# sample.net
KiCad netlist of a schematic drawn in EAGLE
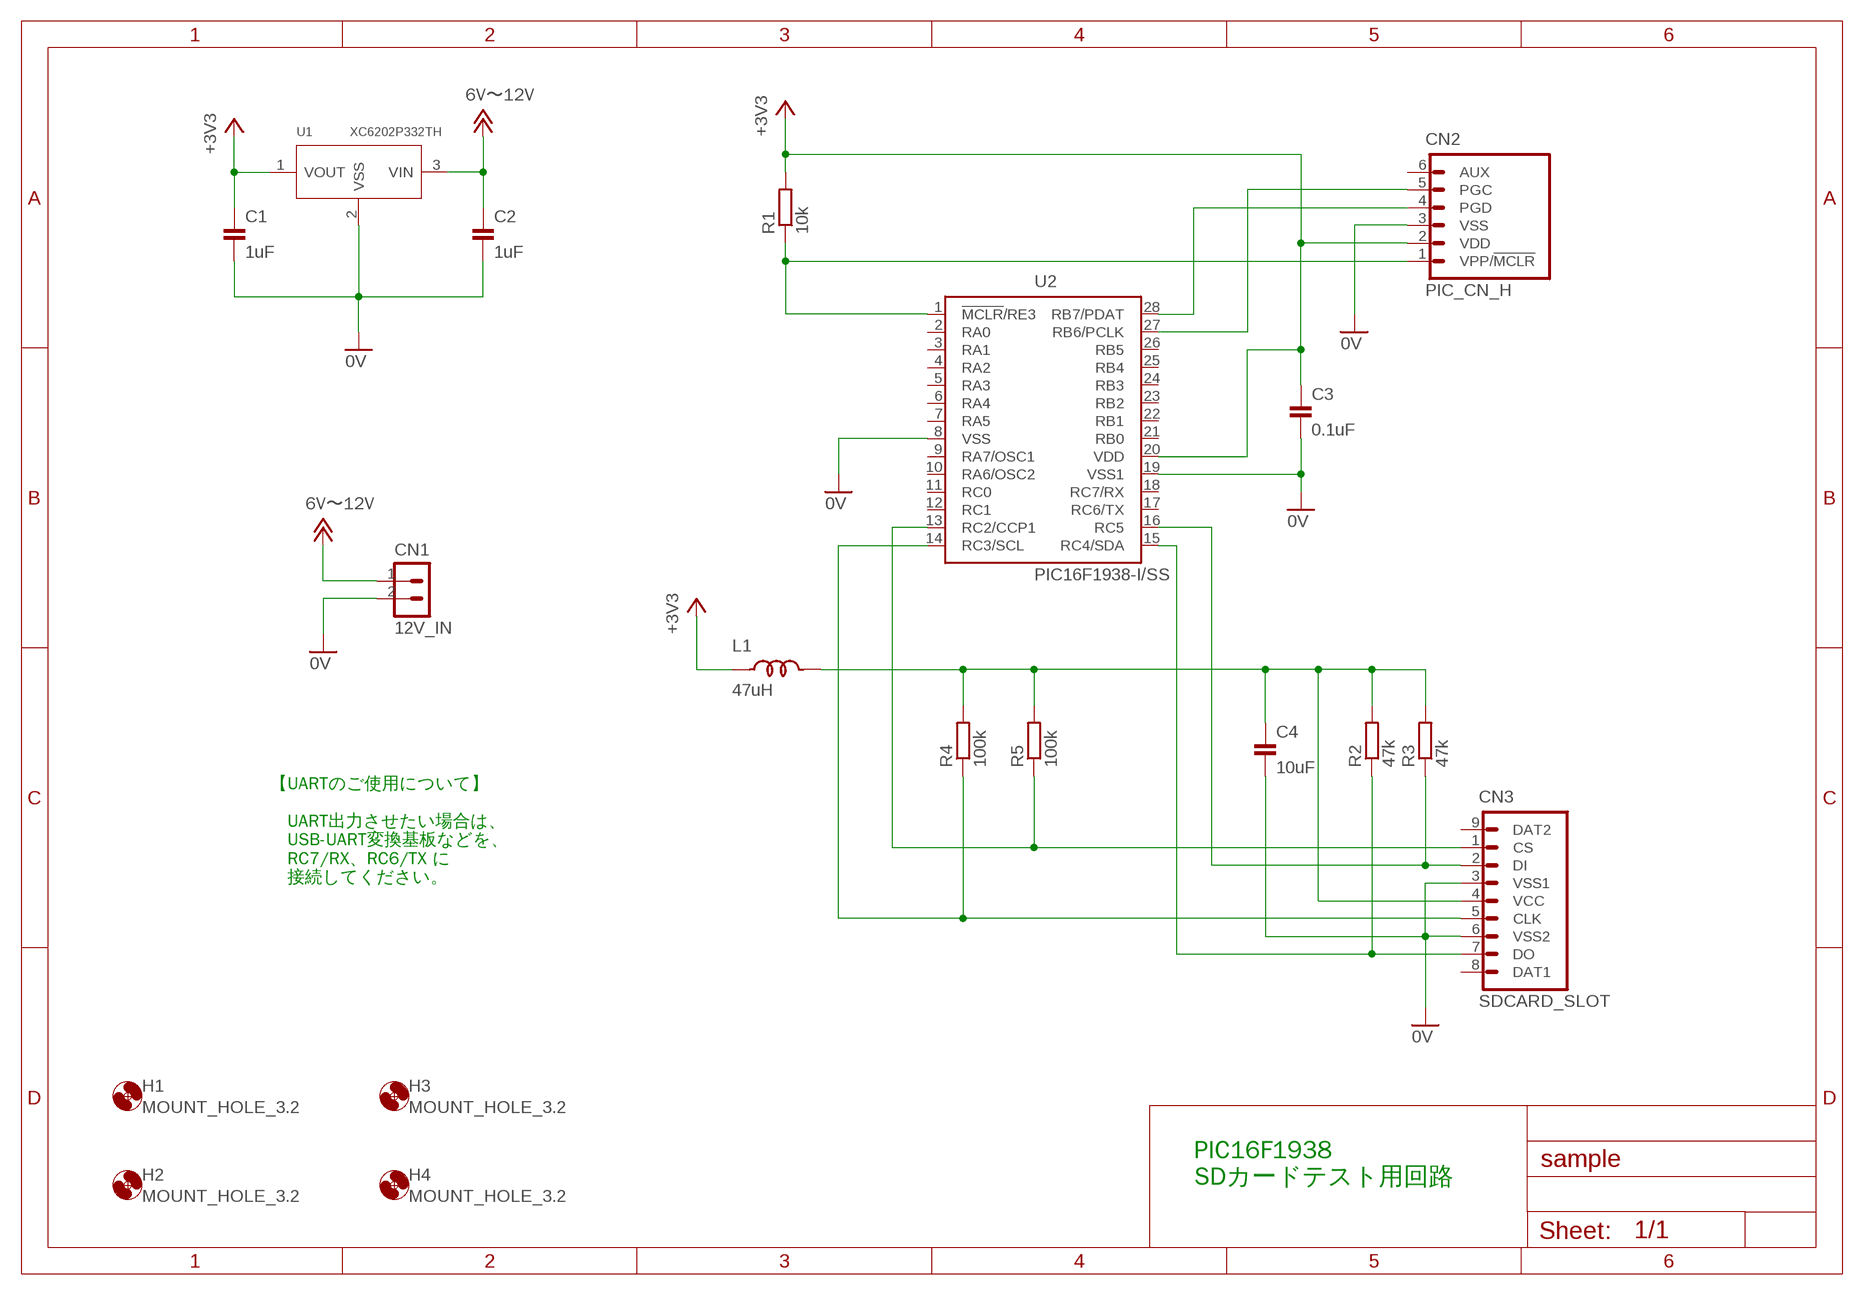
[diagram p0: schematic, sheet 1]

(export (version "E")
  (design (tool "Eeschema 10.0.6"))
  (components
    (comp (ref "C1")
      (value "1uF")
      (footprint "eagle-import:CAP_200MIL")
      (libsource (lib "eagle-import") (part "CAP_200MIL"))
    )
    (comp (ref "C2")
      (value "1uF")
      (footprint "eagle-import:CAP_200MIL")
      (libsource (lib "eagle-import") (part "CAP_200MIL"))
    )
    (comp (ref "C3")
      (value "0.1uF")
      (footprint "eagle-import:CAP_200MIL")
      (libsource (lib "eagle-import") (part "CAP_200MIL"))
    )
    (comp (ref "C4")
      (value "10uF")
      (footprint "eagle-import:CAP_200MIL")
      (libsource (lib "eagle-import") (part "CAP_200MIL"))
    )
    (comp (ref "CN1")
      (value "12V_IN")
      (footprint "eagle-import:HEADER_L_2PIN")
      (libsource (lib "eagle-import") (part "CONN_2PIN-L"))
    )
    (comp (ref "CN2")
      (value "PIC_CN_H")
      (footprint "eagle-import:HEADER_6PIN")
      (libsource (lib "eagle-import") (part "PIC_CN_H"))
    )
    (comp (ref "CN3")
      (value "SDCARD_SLOT")
      (footprint "eagle-import:SDCARD_SLOT")
      (libsource (lib "eagle-import") (part "SDCARD_SLOT"))
    )
    (comp (ref "H1")
      (value "MOUNT_HOLE_3.2")
      (footprint "eagle-import:3,2")
      (libsource (lib "eagle-import") (part "MOUNT_HOLE_3.2"))
    )
    (comp (ref "H2")
      (value "MOUNT_HOLE_3.2")
      (footprint "eagle-import:3,2")
      (libsource (lib "eagle-import") (part "MOUNT_HOLE_3.2"))
    )
    (comp (ref "H3")
      (value "MOUNT_HOLE_3.2")
      (footprint "eagle-import:3,2")
      (libsource (lib "eagle-import") (part "MOUNT_HOLE_3.2"))
    )
    (comp (ref "H4")
      (value "MOUNT_HOLE_3.2")
      (footprint "eagle-import:3,2")
      (libsource (lib "eagle-import") (part "MOUNT_HOLE_3.2"))
    )
    (comp (ref "L1")
      (value "47uH")
      (footprint "eagle-import:TOROID_COIL-300MIL")
      (libsource (lib "eagle-import") (part "TC5026-22UH-060"))
    )
    (comp (ref "R1")
      (value "10k")
      (footprint "eagle-import:RESISTOR_0207_300MIL")
      (libsource (lib "eagle-import") (part "RESISTOR_300MIL"))
    )
    (comp (ref "R2")
      (value "47k")
      (footprint "eagle-import:RESISTOR_0207_300MIL")
      (libsource (lib "eagle-import") (part "RESISTOR_300MIL"))
    )
    (comp (ref "R3")
      (value "47k")
      (footprint "eagle-import:RESISTOR_0207_300MIL")
      (libsource (lib "eagle-import") (part "RESISTOR_300MIL"))
    )
    (comp (ref "R4")
      (value "100k")
      (footprint "eagle-import:RESISTOR_0207_300MIL")
      (libsource (lib "eagle-import") (part "RESISTOR_300MIL"))
    )
    (comp (ref "R5")
      (value "100k")
      (footprint "eagle-import:RESISTOR_0207_300MIL")
      (libsource (lib "eagle-import") (part "RESISTOR_300MIL"))
    )
    (comp (ref "U1")
      (value "XC6202P332TH")
      (footprint "eagle-import:TO92-LINE")
      (libsource (lib "eagle-import") (part "XC6202P332TH"))
    )
    (comp (ref "U2")
      (value "PIC16F1938-I/SS")
      (footprint "eagle-import:SSOP28")
      (libsource (lib "eagle-import") (part "PIC16F1938-I/SS"))
    )
  )
  (nets
    (net (code "1") (name "+3V3") (class "Default")
      (node (ref "C1") (pin "1") (pinfunction "1_1") (pintype "passive"))
      (node (ref "C3") (pin "1") (pinfunction "1_1") (pintype "passive"))
      (node (ref "CN2") (pin "2") (pinfunction "VDD_2") (pintype "passive"))
      (node (ref "L1") (pin "1") (pinfunction "1_1") (pintype "passive"))
      (node (ref "R1") (pin "2") (pinfunction "2_2") (pintype "passive"))
      (node (ref "U1") (pin "1") (pinfunction "VOUT_1") (pintype "passive"))
      (node (ref "U2") (pin "20") (pinfunction "VDD_20") (pintype "passive"))
    )
    (net (code "2") (name "0V") (class "Default")
      (node (ref "C1") (pin "2") (pinfunction "2_2") (pintype "passive"))
      (node (ref "C2") (pin "2") (pinfunction "2_2") (pintype "passive"))
      (node (ref "C3") (pin "2") (pinfunction "2_2") (pintype "passive"))
      (node (ref "C4") (pin "2") (pinfunction "2_2") (pintype "passive"))
      (node (ref "CN1") (pin "2") (pinfunction "2_2") (pintype "passive"))
      (node (ref "CN2") (pin "3") (pinfunction "VSS_3") (pintype "passive"))
      (node (ref "CN3") (pin "3") (pinfunction "VSS1_3") (pintype "passive"))
      (node (ref "CN3") (pin "6") (pinfunction "VSS2_6") (pintype "passive"))
      (node (ref "U1") (pin "2") (pinfunction "VSS_2") (pintype "passive"))
      (node (ref "U2") (pin "19") (pinfunction "VSS1_19") (pintype "passive"))
      (node (ref "U2") (pin "8") (pinfunction "VSS_8") (pintype "passive"))
    )
    (net (code "3") (name "6V〜12V") (class "Default")
      (node (ref "C2") (pin "1") (pinfunction "1_1") (pintype "passive"))
      (node (ref "CN1") (pin "1") (pinfunction "1_1") (pintype "passive"))
      (node (ref "U1") (pin "3") (pinfunction "VIN_3") (pintype "passive"))
    )
    (net (code "4") (name "Net-(CN2-PGC)") (class "Default")
      (node (ref "CN2") (pin "5") (pinfunction "PGC_5") (pintype "input"))
      (node (ref "U2") (pin "27") (pinfunction "RB6/PCLK_27") (pintype "bidirectional"))
    )
    (net (code "5") (name "Net-(CN2-PGD)") (class "Default")
      (node (ref "CN2") (pin "4") (pinfunction "PGD_4") (pintype "bidirectional"))
      (node (ref "U2") (pin "28") (pinfunction "RB7/PDAT_28") (pintype "bidirectional"))
    )
    (net (code "6") (name "Net-(CN2-VPP{slash}~{MCLR})") (class "Default")
      (node (ref "CN2") (pin "1") (pinfunction "VPP/~{MCLR}_1") (pintype "input"))
      (node (ref "R1") (pin "1") (pinfunction "1_1") (pintype "passive"))
      (node (ref "U2") (pin "1") (pinfunction "~{MCLR}/RE3_1") (pintype "bidirectional"))
    )
    (net (code "7") (name "Net-(CN3-CLK)") (class "Default")
      (node (ref "CN3") (pin "5") (pinfunction "CLK_5") (pintype "bidirectional"))
      (node (ref "R4") (pin "1") (pinfunction "1_1") (pintype "passive"))
      (node (ref "U2") (pin "14") (pinfunction "RC3/SCL_14") (pintype "bidirectional"))
    )
    (net (code "8") (name "Net-(CN3-CS)") (class "Default")
      (node (ref "CN3") (pin "1") (pinfunction "CS_1") (pintype "bidirectional"))
      (node (ref "R5") (pin "1") (pinfunction "1_1") (pintype "passive"))
      (node (ref "U2") (pin "13") (pinfunction "RC2/CCP1_13") (pintype "bidirectional"))
    )
    (net (code "9") (name "Net-(CN3-DI)") (class "Default")
      (node (ref "CN3") (pin "2") (pinfunction "DI_2") (pintype "bidirectional"))
      (node (ref "R3") (pin "1") (pinfunction "1_1") (pintype "passive"))
      (node (ref "U2") (pin "16") (pinfunction "RC5_16") (pintype "bidirectional"))
    )
    (net (code "10") (name "Net-(CN3-DO)") (class "Default")
      (node (ref "CN3") (pin "7") (pinfunction "DO_7") (pintype "bidirectional"))
      (node (ref "R2") (pin "1") (pinfunction "1_1") (pintype "passive"))
      (node (ref "U2") (pin "15") (pinfunction "RC4/SDA_15") (pintype "bidirectional"))
    )
    (net (code "11") (name "Net-(CN3-VCC)") (class "Default")
      (node (ref "C4") (pin "1") (pinfunction "1_1") (pintype "passive"))
      (node (ref "CN3") (pin "4") (pinfunction "VCC_4") (pintype "passive"))
      (node (ref "L1") (pin "2") (pinfunction "2_2") (pintype "passive"))
      (node (ref "R2") (pin "2") (pinfunction "2_2") (pintype "passive"))
      (node (ref "R3") (pin "2") (pinfunction "2_2") (pintype "passive"))
      (node (ref "R4") (pin "2") (pinfunction "2_2") (pintype "passive"))
      (node (ref "R5") (pin "2") (pinfunction "2_2") (pintype "passive"))
    )
    (net (code "12") (name "unconnected-(CN2-AUX-Pad6)") (class "Default")
      (node (ref "CN2") (pin "6") (pinfunction "AUX_6") (pintype "bidirectional"))
    )
    (net (code "13") (name "unconnected-(CN3-DAT1-Pad8)") (class "Default")
      (node (ref "CN3") (pin "8") (pinfunction "DAT1_8") (pintype "bidirectional"))
    )
    (net (code "14") (name "unconnected-(CN3-DAT2-Pad9)") (class "Default")
      (node (ref "CN3") (pin "9") (pinfunction "DAT2_9") (pintype "bidirectional"))
    )
    (net (code "15") (name "unconnected-(U2-RA0-Pad2)") (class "Default")
      (node (ref "U2") (pin "2") (pinfunction "RA0_2") (pintype "bidirectional"))
    )
    (net (code "16") (name "unconnected-(U2-RA1-Pad3)") (class "Default")
      (node (ref "U2") (pin "3") (pinfunction "RA1_3") (pintype "bidirectional"))
    )
    (net (code "17") (name "unconnected-(U2-RA2-Pad4)") (class "Default")
      (node (ref "U2") (pin "4") (pinfunction "RA2_4") (pintype "bidirectional"))
    )
    (net (code "18") (name "unconnected-(U2-RA3-Pad5)") (class "Default")
      (node (ref "U2") (pin "5") (pinfunction "RA3_5") (pintype "bidirectional"))
    )
    (net (code "19") (name "unconnected-(U2-RA4-Pad6)") (class "Default")
      (node (ref "U2") (pin "6") (pinfunction "RA4_6") (pintype "bidirectional"))
    )
    (net (code "20") (name "unconnected-(U2-RA5-Pad7)") (class "Default")
      (node (ref "U2") (pin "7") (pinfunction "RA5_7") (pintype "bidirectional"))
    )
    (net (code "21") (name "unconnected-(U2-RA6{slash}OSC2-Pad10)") (class "Default")
      (node (ref "U2") (pin "10") (pinfunction "RA6/OSC2_10") (pintype "bidirectional"))
    )
    (net (code "22") (name "unconnected-(U2-RA7{slash}OSC1-Pad9)") (class "Default")
      (node (ref "U2") (pin "9") (pinfunction "RA7/OSC1_9") (pintype "bidirectional"))
    )
    (net (code "23") (name "unconnected-(U2-RB0-Pad21)") (class "Default")
      (node (ref "U2") (pin "21") (pinfunction "RB0_21") (pintype "bidirectional"))
    )
    (net (code "24") (name "unconnected-(U2-RB1-Pad22)") (class "Default")
      (node (ref "U2") (pin "22") (pinfunction "RB1_22") (pintype "bidirectional"))
    )
    (net (code "25") (name "unconnected-(U2-RB2-Pad23)") (class "Default")
      (node (ref "U2") (pin "23") (pinfunction "RB2_23") (pintype "bidirectional"))
    )
    (net (code "26") (name "unconnected-(U2-RB3-Pad24)") (class "Default")
      (node (ref "U2") (pin "24") (pinfunction "RB3_24") (pintype "bidirectional"))
    )
    (net (code "27") (name "unconnected-(U2-RB4-Pad25)") (class "Default")
      (node (ref "U2") (pin "25") (pinfunction "RB4_25") (pintype "bidirectional"))
    )
    (net (code "28") (name "unconnected-(U2-RB5-Pad26)") (class "Default")
      (node (ref "U2") (pin "26") (pinfunction "RB5_26") (pintype "bidirectional"))
    )
    (net (code "29") (name "unconnected-(U2-RC0-Pad11)") (class "Default")
      (node (ref "U2") (pin "11") (pinfunction "RC0_11") (pintype "bidirectional"))
    )
    (net (code "30") (name "unconnected-(U2-RC1-Pad12)") (class "Default")
      (node (ref "U2") (pin "12") (pinfunction "RC1_12") (pintype "bidirectional"))
    )
    (net (code "31") (name "unconnected-(U2-RC6{slash}TX-Pad17)") (class "Default")
      (node (ref "U2") (pin "17") (pinfunction "RC6/TX_17") (pintype "bidirectional"))
    )
    (net (code "32") (name "unconnected-(U2-RC7{slash}RX-Pad18)") (class "Default")
      (node (ref "U2") (pin "18") (pinfunction "RC7/RX_18") (pintype "bidirectional"))
    )
  )
)
